# gyroscope.net
KiCad netlist of a schematic drawn in Altium Designer
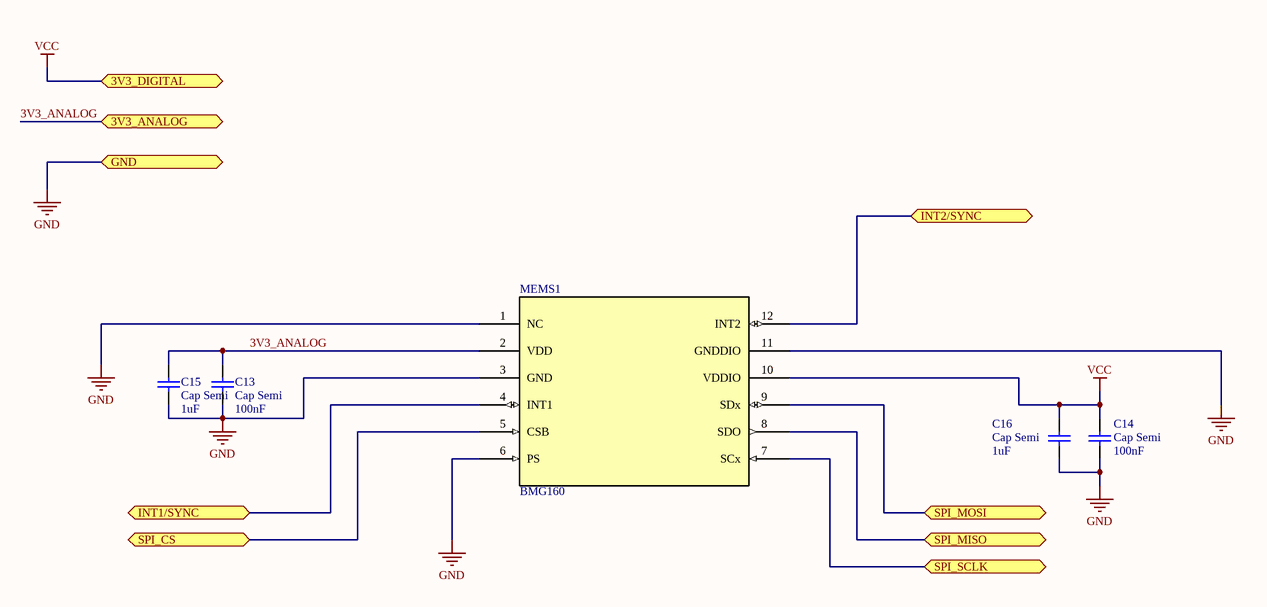
[diagram p0: gyroscope.SchDoc]

(export (version "E")
  (design (tool "Eeschema 10.0.6"))
  (components
    (comp (ref "C13")
      (value "Cap Semi")
      (footprint "C1206")
      (description "Capacitor (Semiconductor SIM Model)")
      (fields (field (name "ALTIUM_VALUE") "100nF") (field (name "PUBLISHER") "Altium Limited"))
      (libsource (lib "Miscellaneous Devices") (part "Cap Semi"))
    )
    (comp (ref "C14")
      (value "Cap Semi")
      (footprint "C1206")
      (description "Capacitor (Semiconductor SIM Model)")
      (fields (field (name "ALTIUM_VALUE") "100nF") (field (name "PUBLISHER") "Altium Limited"))
      (libsource (lib "Miscellaneous Devices") (part "Cap Semi"))
    )
    (comp (ref "C15")
      (value "Cap Semi")
      (footprint "C1210")
      (description "Capacitor (Semiconductor SIM Model)")
      (fields (field (name "ALTIUM_VALUE") "1uF") (field (name "PUBLISHER") "Altium Limited"))
      (libsource (lib "Miscellaneous Devices") (part "Cap Semi"))
    )
    (comp (ref "C16")
      (value "Cap Semi")
      (footprint "C1210")
      (description "Capacitor (Semiconductor SIM Model)")
      (fields (field (name "ALTIUM_VALUE") "1uF") (field (name "PUBLISHER") "Altium Limited"))
      (libsource (lib "Miscellaneous Devices") (part "Cap Semi"))
    )
    (comp (ref "MEMS1")
      (value "BMG160")
      (footprint "RPi_sensor_expansion_board:LGA12-BOSCH")
      (libsource (lib "RPi_sensor_expansion_board_library") (part "BMG160"))
    )
  )
  (nets
    (net (code "1") (name "/3V3_ANALOG") (class "Default")
      (node (ref "C13") (pin "2") (pinfunction "2_2") (pintype "passive"))
      (node (ref "C15") (pin "2") (pinfunction "2_2") (pintype "passive"))
      (node (ref "MEMS1") (pin "2") (pinfunction "VDD_2") (pintype "power_in"))
    )
    (net (code "2") (name "/INT1{slash}SYNC") (class "Default")
      (node (ref "MEMS1") (pin "4") (pinfunction "INT1_4") (pintype "bidirectional"))
    )
    (net (code "3") (name "/INT2{slash}SYNC") (class "Default")
      (node (ref "MEMS1") (pin "12") (pinfunction "INT2_12") (pintype "bidirectional"))
    )
    (net (code "4") (name "/SPI_CS") (class "Default")
      (node (ref "MEMS1") (pin "5") (pinfunction "CSB_5") (pintype "input"))
    )
    (net (code "5") (name "/SPI_MISO") (class "Default")
      (node (ref "MEMS1") (pin "8") (pinfunction "SDO_8") (pintype "output"))
    )
    (net (code "6") (name "/SPI_MOSI") (class "Default")
      (node (ref "MEMS1") (pin "9") (pinfunction "SDx_9") (pintype "bidirectional"))
    )
    (net (code "7") (name "/SPI_SCLK") (class "Default")
      (node (ref "MEMS1") (pin "7") (pinfunction "SCx_7") (pintype "input"))
    )
    (net (code "8") (name "GND") (class "Default")
      (node (ref "C13") (pin "1") (pinfunction "1_1") (pintype "passive"))
      (node (ref "C14") (pin "1") (pinfunction "1_1") (pintype "passive"))
      (node (ref "C15") (pin "1") (pinfunction "1_1") (pintype "passive"))
      (node (ref "C16") (pin "1") (pinfunction "1_1") (pintype "passive"))
      (node (ref "MEMS1") (pin "1") (pinfunction "NC_1") (pintype "passive"))
      (node (ref "MEMS1") (pin "11") (pinfunction "GNDDIO_11") (pintype "power_in"))
      (node (ref "MEMS1") (pin "3") (pinfunction "GND_3") (pintype "power_in"))
      (node (ref "MEMS1") (pin "6") (pinfunction "PS_6") (pintype "input"))
    )
    (net (code "9") (name "VCC") (class "Default")
      (node (ref "C14") (pin "2") (pinfunction "2_2") (pintype "passive"))
      (node (ref "C16") (pin "2") (pinfunction "2_2") (pintype "passive"))
      (node (ref "MEMS1") (pin "10") (pinfunction "VDDIO_10") (pintype "power_in"))
    )
  )
)
